# ESP8266-ESP12_IoT.net
KiCad netlist of a schematic drawn in EAGLE
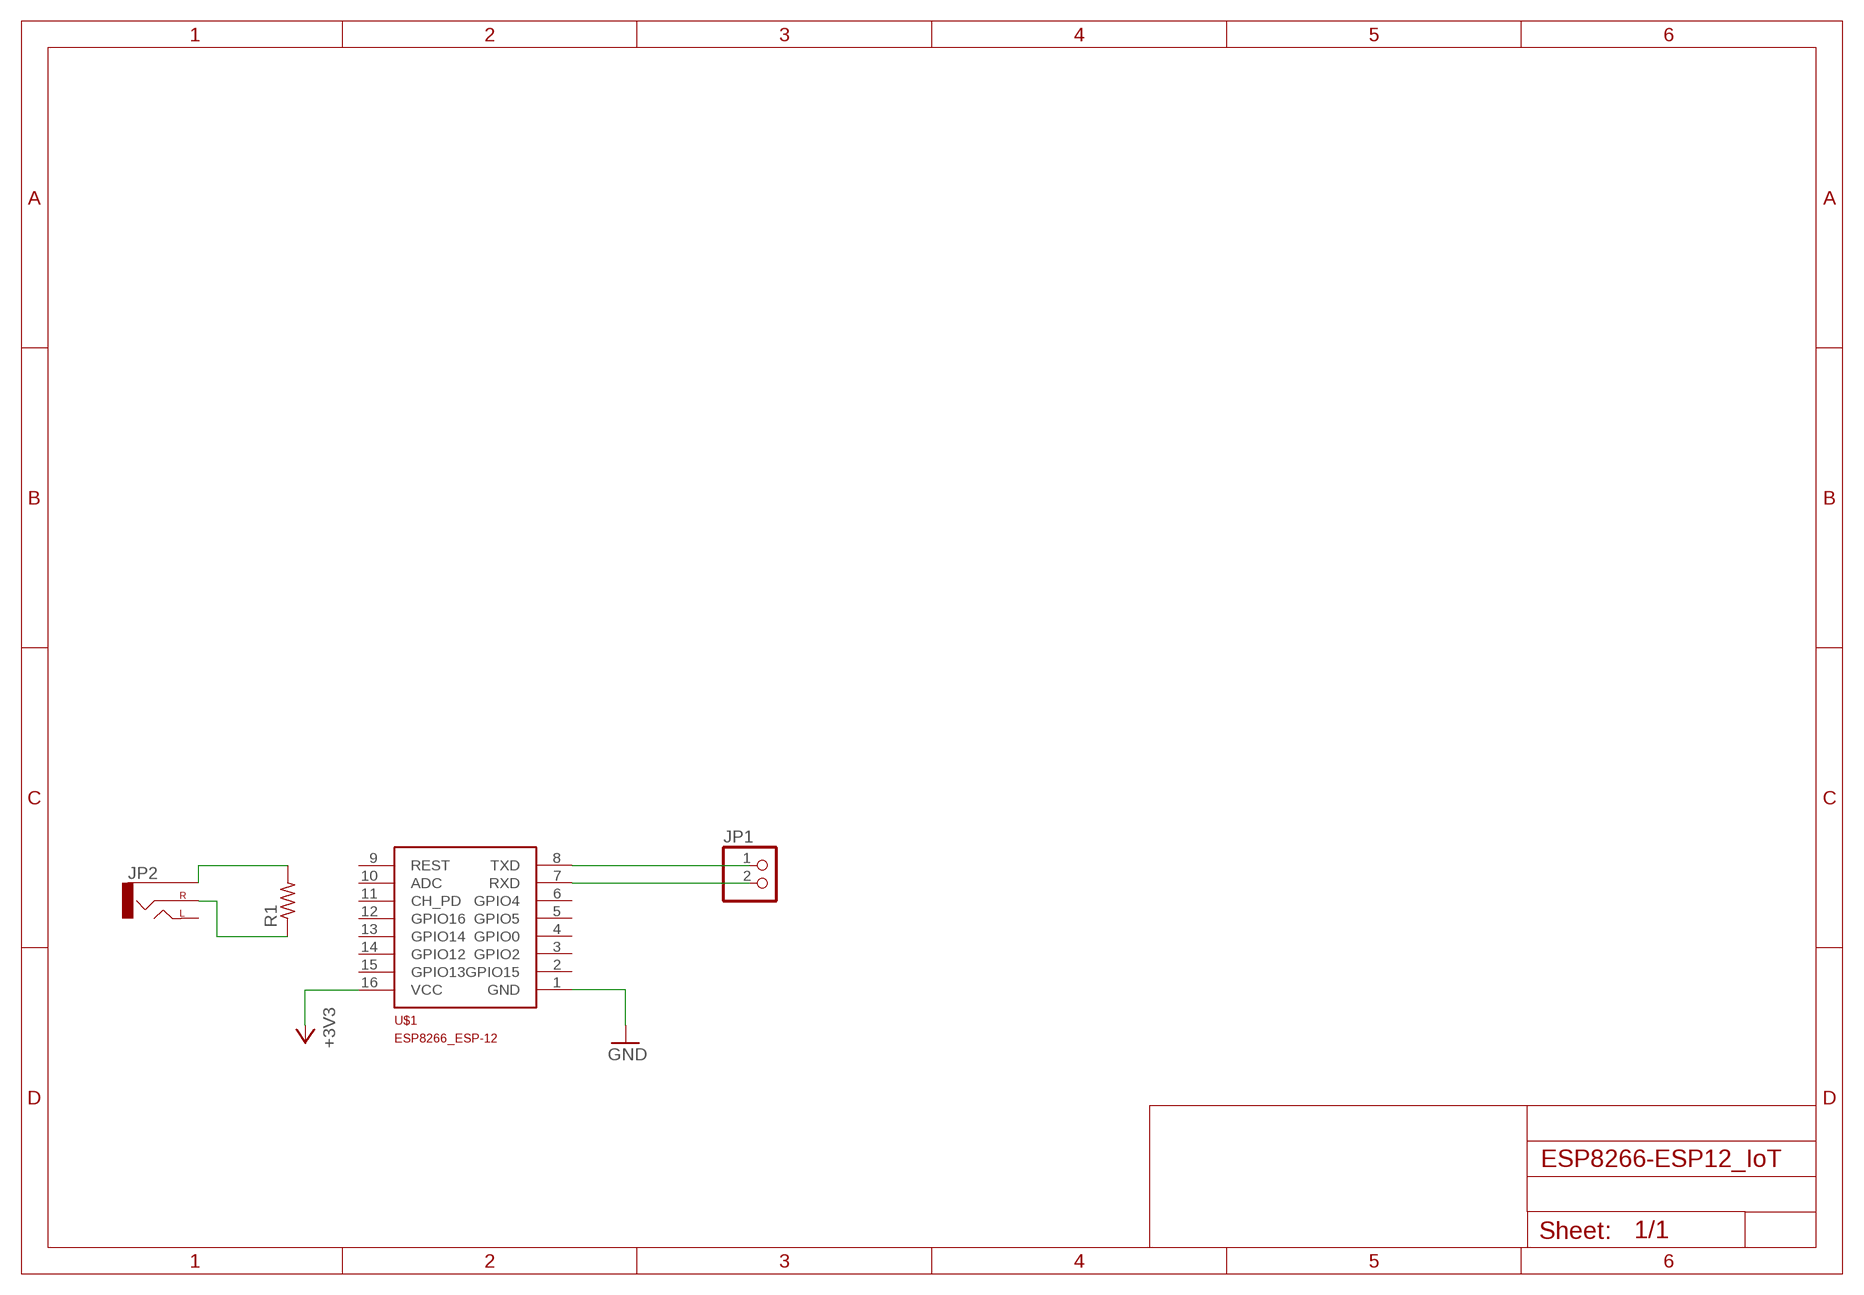
[diagram p0: schematic, sheet 1]

(export (version "E")
  (design (tool "Eeschema 10.0.6"))
  (components
    (comp (ref "JP1")
      (value "PINHD-1X2/90")
      (footprint "eagle-import:1X02_90")
      (libsource (lib "eagle-import") (part "PINHD-1X2/90"))
    )
    (comp (ref "JP2")
      (value "AUDIO-JACKPTH")
      (footprint "eagle-import:AUDIO-JACK")
      (libsource (lib "eagle-import") (part "AUDIO-JACKPTH"))
    )
    (comp (ref "R1")
      (value "R-US_R0805")
      (footprint "eagle-import:R0805")
      (libsource (lib "eagle-import") (part "R-US_R0805"))
    )
    (comp (ref "U$1")
      (value "ESP8266_ESP-12")
      (footprint "eagle-import:ESP8266-ESP12")
      (libsource (lib "eagle-import") (part "ESP8266_ESP-12"))
    )
  )
  (nets
    (net (code "1") (name "+3V3") (class "Default")
      (node (ref "U$1") (pin "16") (pinfunction "VCC_16") (pintype "bidirectional"))
    )
    (net (code "2") (name "GND") (class "Default")
      (node (ref "U$1") (pin "1") (pinfunction "GND_1") (pintype "bidirectional"))
    )
    (net (code "3") (name "Net-(JP2-PadSLEEVE)") (class "Default")
      (node (ref "JP2") (pin "SLEEVE") (pinfunction "SLEEVE_SLEEVE") (pintype "bidirectional"))
      (node (ref "R1") (pin "2") (pinfunction "2_2") (pintype "passive"))
    )
    (net (code "4") (name "Net-(JP2-RIGHT)") (class "Default")
      (node (ref "JP2") (pin "RING") (pinfunction "RIGHT_RING") (pintype "bidirectional"))
      (node (ref "R1") (pin "1") (pinfunction "1_1") (pintype "passive"))
    )
    (net (code "5") (name "Net-(U$1-RXD)") (class "Default")
      (node (ref "JP1") (pin "2") (pinfunction "2_2") (pintype "passive"))
      (node (ref "U$1") (pin "7") (pinfunction "RXD_7") (pintype "bidirectional"))
    )
    (net (code "6") (name "Net-(U$1-TXD)") (class "Default")
      (node (ref "JP1") (pin "1") (pinfunction "1_1") (pintype "passive"))
      (node (ref "U$1") (pin "8") (pinfunction "TXD_8") (pintype "bidirectional"))
    )
    (net (code "7") (name "unconnected-(JP2-LEFT-PadTIP)") (class "Default")
      (node (ref "JP2") (pin "TIP") (pinfunction "LEFT_TIP") (pintype "bidirectional"))
    )
    (net (code "8") (name "unconnected-(U$1-ADC-Pad10)") (class "Default")
      (node (ref "U$1") (pin "10") (pinfunction "ADC_10") (pintype "bidirectional"))
    )
    (net (code "9") (name "unconnected-(U$1-CH_PD-Pad11)") (class "Default")
      (node (ref "U$1") (pin "11") (pinfunction "CH_PD_11") (pintype "bidirectional"))
    )
    (net (code "10") (name "unconnected-(U$1-GPIO0-Pad4)") (class "Default")
      (node (ref "U$1") (pin "4") (pinfunction "GPIO0_4") (pintype "bidirectional"))
    )
    (net (code "11") (name "unconnected-(U$1-GPIO2-Pad3)") (class "Default")
      (node (ref "U$1") (pin "3") (pinfunction "GPIO2_3") (pintype "bidirectional"))
    )
    (net (code "12") (name "unconnected-(U$1-GPIO4-Pad6)") (class "Default")
      (node (ref "U$1") (pin "6") (pinfunction "GPIO4_6") (pintype "bidirectional"))
    )
    (net (code "13") (name "unconnected-(U$1-GPIO5-Pad5)") (class "Default")
      (node (ref "U$1") (pin "5") (pinfunction "GPIO5_5") (pintype "bidirectional"))
    )
    (net (code "14") (name "unconnected-(U$1-GPIO12-Pad14)") (class "Default")
      (node (ref "U$1") (pin "14") (pinfunction "GPIO12_14") (pintype "bidirectional"))
    )
    (net (code "15") (name "unconnected-(U$1-GPIO13-Pad15)") (class "Default")
      (node (ref "U$1") (pin "15") (pinfunction "GPIO13_15") (pintype "bidirectional"))
    )
    (net (code "16") (name "unconnected-(U$1-GPIO14-Pad13)") (class "Default")
      (node (ref "U$1") (pin "13") (pinfunction "GPIO14_13") (pintype "bidirectional"))
    )
    (net (code "17") (name "unconnected-(U$1-GPIO15-Pad2)") (class "Default")
      (node (ref "U$1") (pin "2") (pinfunction "GPIO15_2") (pintype "bidirectional"))
    )
    (net (code "18") (name "unconnected-(U$1-GPIO16-Pad12)") (class "Default")
      (node (ref "U$1") (pin "12") (pinfunction "GPIO16_12") (pintype "bidirectional"))
    )
    (net (code "19") (name "unconnected-(U$1-REST-Pad9)") (class "Default")
      (node (ref "U$1") (pin "9") (pinfunction "REST_9") (pintype "bidirectional"))
    )
  )
)
